# ATXmega_FPC_adapter.net
KiCad netlist of a schematic drawn in EAGLE
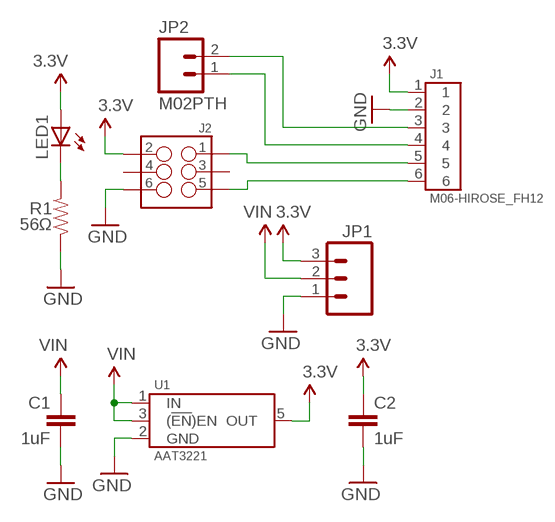
[diagram p0: schematic, sheet 1]

(export (version "E")
  (design (tool "Eeschema 10.0.6"))
  (components
    (comp (ref "C1")
      (value "1uF")
      (footprint "eagle-import:0603-CAP")
      (libsource (lib "eagle-import") (part "CAP0603-CAP"))
    )
    (comp (ref "C2")
      (value "1uF")
      (footprint "eagle-import:0603-CAP")
      (libsource (lib "eagle-import") (part "CAP0603-CAP"))
    )
    (comp (ref "J1")
      (value "M06-HIROSE_FH12")
      (footprint "eagle-import:FH12-6S-1SH(55)")
      (libsource (lib "eagle-import") (part "M06-HIROSE_FH12"))
    )
    (comp (ref "J2")
      (value "M03X2SHROUD")
      (footprint "eagle-import:2X3-SHROUDED")
      (libsource (lib "eagle-import") (part "M03X2SHROUD"))
    )
    (comp (ref "JP1")
      (value "M03PTH")
      (footprint "eagle-import:1X03")
      (libsource (lib "eagle-import") (part "M03PTH"))
    )
    (comp (ref "JP2")
      (value "M02PTH")
      (footprint "eagle-import:1X02")
      (libsource (lib "eagle-import") (part "M02PTH"))
    )
    (comp (ref "LED1")
      (value "LED0603")
      (footprint "eagle-import:LED-0603")
      (libsource (lib "eagle-import") (part "LED0603"))
    )
    (comp (ref "R1")
      (value "56Ω")
      (footprint "eagle-import:0603-RES")
      (libsource (lib "eagle-import") (part "RESISTOR0603-RES"))
    )
    (comp (ref "U1")
      (value "AAT3221")
      (footprint "eagle-import:SOT23-5")
      (libsource (lib "eagle-import") (part "AAT3221"))
    )
  )
  (nets
    (net (code "1") (name "3.3V") (class "Default")
      (node (ref "C2") (pin "1") (pinfunction "1_1") (pintype "passive"))
      (node (ref "J1") (pin "1") (pinfunction "1_1") (pintype "bidirectional"))
      (node (ref "J2") (pin "2") (pinfunction "2_2") (pintype "bidirectional"))
      (node (ref "JP1") (pin "3") (pinfunction "3_3") (pintype "passive"))
      (node (ref "LED1") (pin "A") (pinfunction "A_A") (pintype "passive"))
      (node (ref "U1") (pin "5") (pinfunction "OUT_5") (pintype "bidirectional"))
    )
    (net (code "2") (name "GND") (class "Default")
      (node (ref "C1") (pin "2") (pinfunction "2_2") (pintype "passive"))
      (node (ref "C2") (pin "2") (pinfunction "2_2") (pintype "passive"))
      (node (ref "J1") (pin "2") (pinfunction "2_2") (pintype "bidirectional"))
      (node (ref "J2") (pin "6") (pinfunction "6_6") (pintype "bidirectional"))
      (node (ref "JP1") (pin "1") (pinfunction "1_1") (pintype "passive"))
      (node (ref "R1") (pin "1") (pinfunction "1_1") (pintype "passive"))
      (node (ref "U1") (pin "2") (pinfunction "GND_2") (pintype "bidirectional"))
    )
    (net (code "3") (name "Net-(J1-Pad3)") (class "Default")
      (node (ref "J1") (pin "3") (pinfunction "3_3") (pintype "bidirectional"))
      (node (ref "JP2") (pin "2") (pinfunction "2_2") (pintype "passive"))
    )
    (net (code "4") (name "Net-(J1-Pad4)") (class "Default")
      (node (ref "J1") (pin "4") (pinfunction "4_4") (pintype "bidirectional"))
      (node (ref "JP2") (pin "1") (pinfunction "1_1") (pintype "passive"))
    )
    (net (code "5") (name "Net-(J1-Pad5)") (class "Default")
      (node (ref "J1") (pin "5") (pinfunction "5_5") (pintype "bidirectional"))
      (node (ref "J2") (pin "1") (pinfunction "1_1") (pintype "bidirectional"))
    )
    (net (code "6") (name "Net-(J1-Pad6)") (class "Default")
      (node (ref "J1") (pin "6") (pinfunction "6_6") (pintype "bidirectional"))
      (node (ref "J2") (pin "5") (pinfunction "5_5") (pintype "bidirectional"))
    )
    (net (code "7") (name "Net-(LED1-PadC)") (class "Default")
      (node (ref "LED1") (pin "C") (pinfunction "C_C") (pintype "passive"))
      (node (ref "R1") (pin "2") (pinfunction "2_2") (pintype "passive"))
    )
    (net (code "8") (name "VIN") (class "Default")
      (node (ref "C1") (pin "1") (pinfunction "1_1") (pintype "passive"))
      (node (ref "JP1") (pin "2") (pinfunction "2_2") (pintype "passive"))
      (node (ref "U1") (pin "1") (pinfunction "IN_1") (pintype "bidirectional"))
      (node (ref "U1") (pin "3") (pinfunction "(~{EN})EN_3") (pintype "bidirectional"))
    )
    (net (code "9") (name "unconnected-(J2-Pad3)") (class "Default")
      (node (ref "J2") (pin "3") (pinfunction "3_3") (pintype "bidirectional"))
    )
    (net (code "10") (name "unconnected-(J2-Pad4)") (class "Default")
      (node (ref "J2") (pin "4") (pinfunction "4_4") (pintype "bidirectional"))
    )
  )
)
